# Acoustic_recorder.net
KiCad netlist of a schematic drawn in Altium Designer
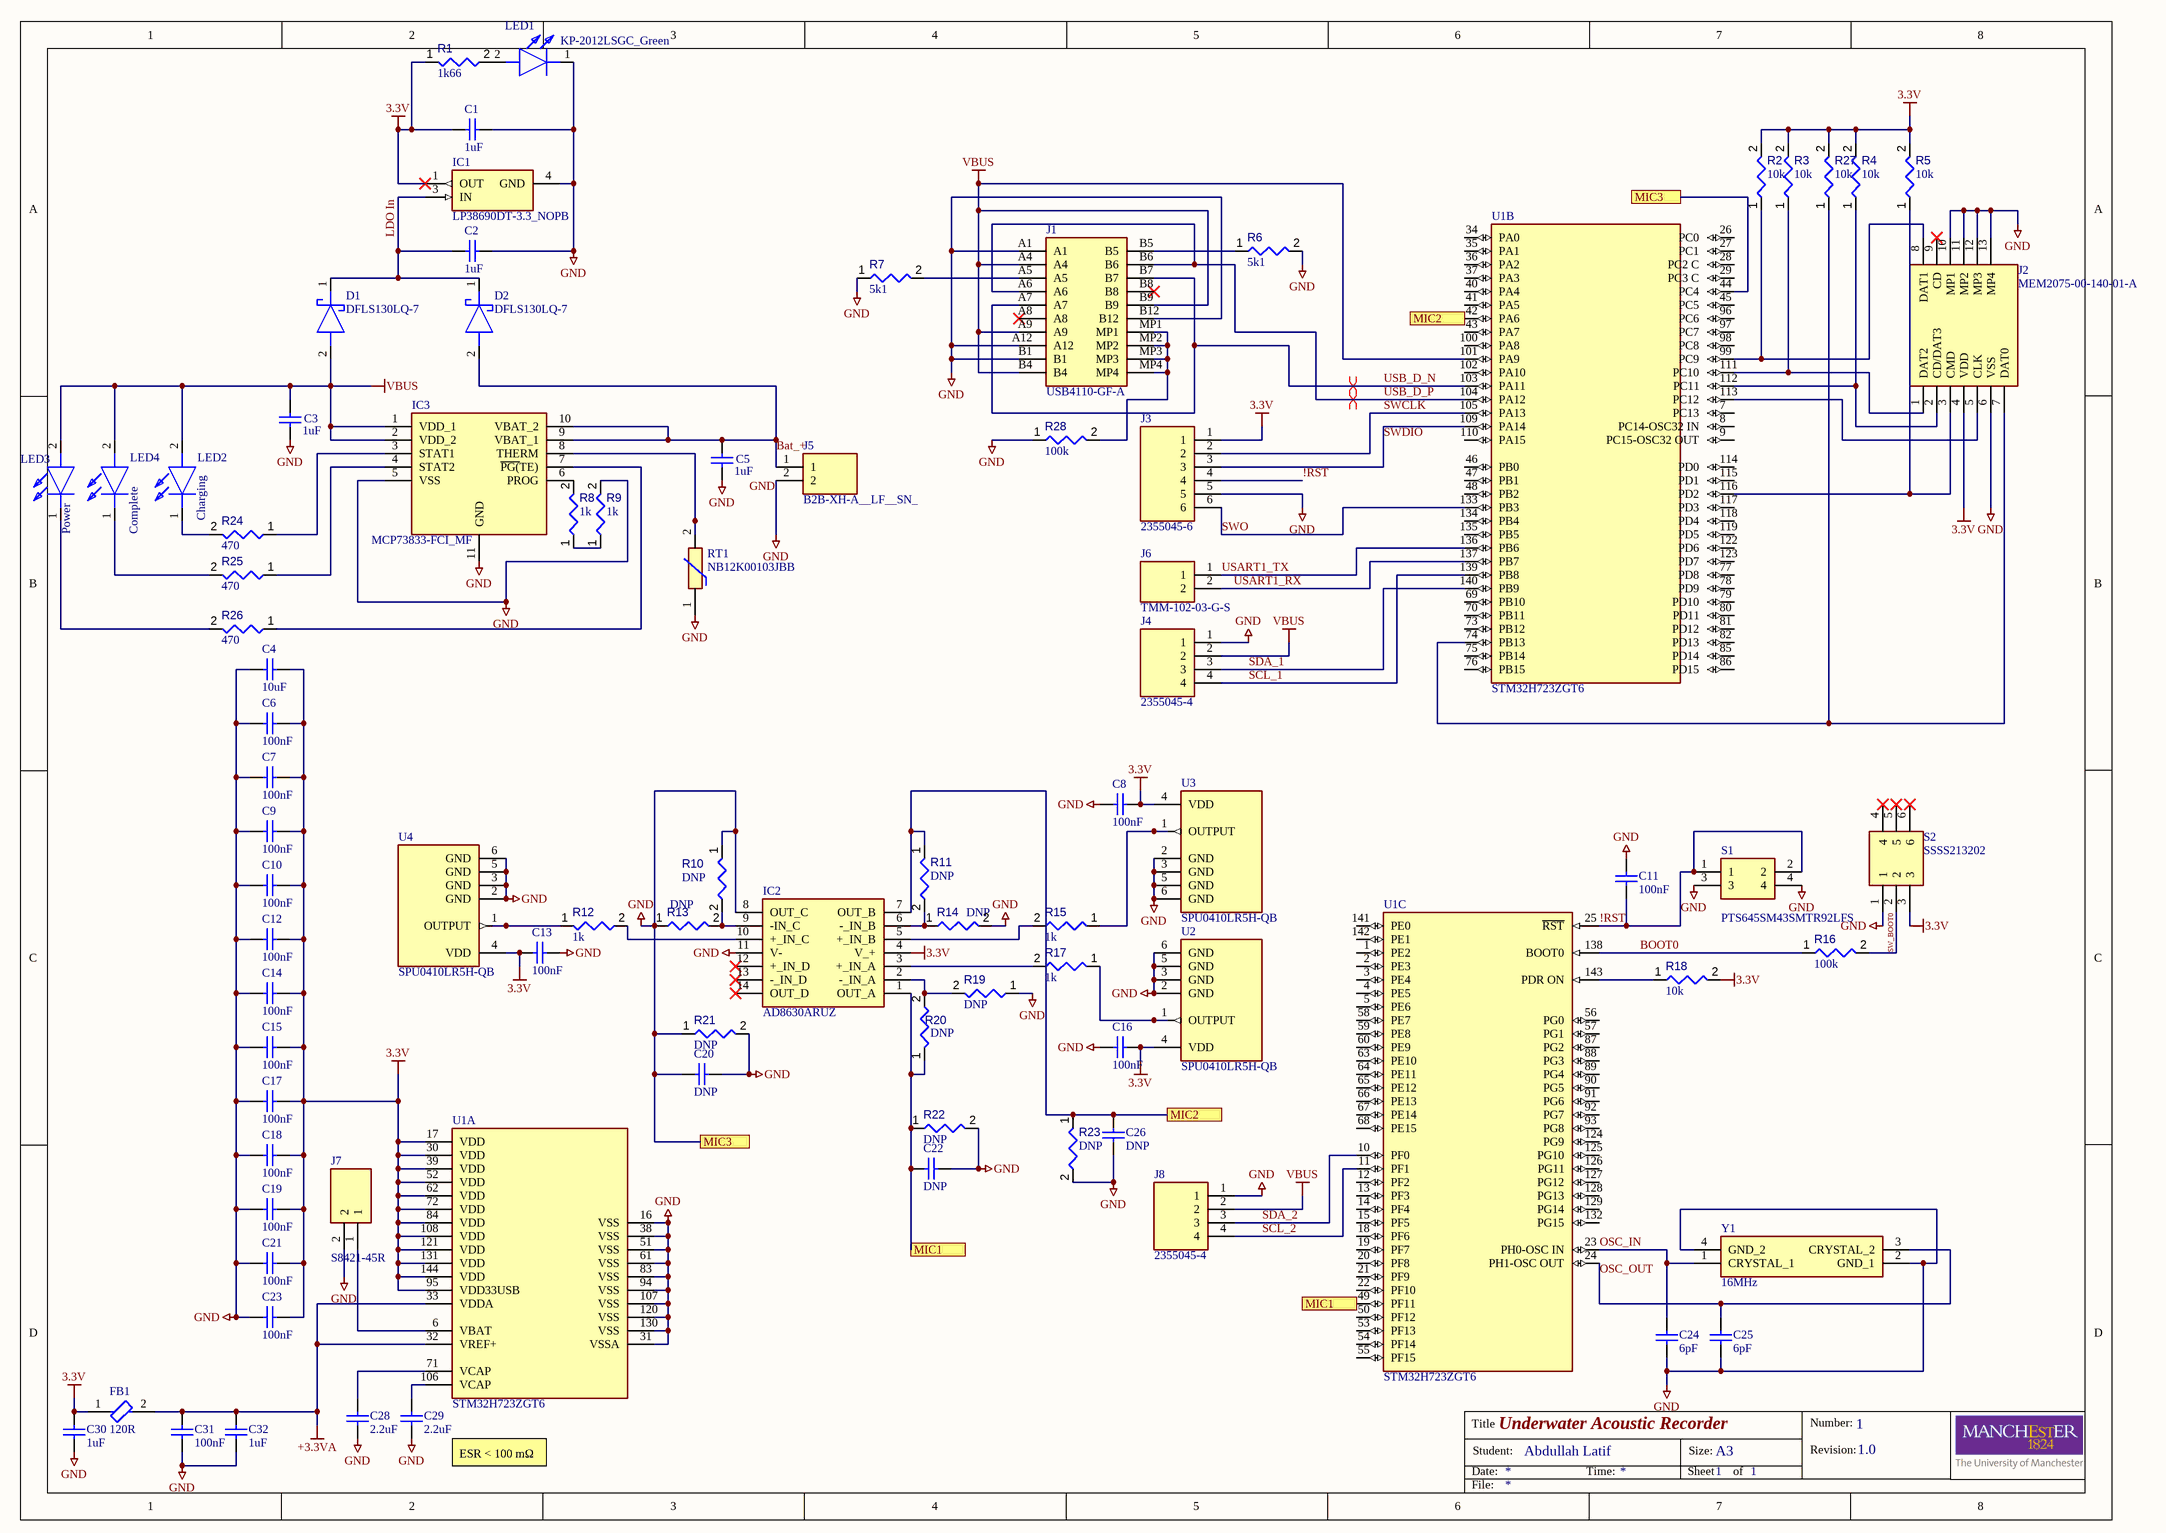
[diagram p0: Acoustic recorder.SchDoc]

(export (version "E")
  (design (tool "Eeschema 10.0.6"))
  (components
    (comp (ref "C1")
      (value "1uF")
      (footprint "CAPC2013X145X50LL20T25")
      (fields (field (name "MANUFACTURER") "Kemet") (field (name "PART NUMBER") "C0805C104K9RACTU"))
      (libsource (lib "Altium Content Vault") (part "CAP"))
    )
    (comp (ref "C2")
      (value "1uF")
      (footprint "CAPC2013X145X50LL20T25")
      (fields (field (name "MANUFACTURER") "Kemet") (field (name "PART NUMBER") "C0805C104K9RACTU"))
      (libsource (lib "Altium Content Vault") (part "CAP"))
    )
    (comp (ref "C3")
      (value "1uF")
      (footprint "CAPC2013X145X50LL20T25")
      (fields (field (name "MANUFACTURER") "Kemet") (field (name "PART NUMBER") "C0805C104K9RACTU"))
      (libsource (lib "Altium Content Vault") (part "CAP"))
    )
    (comp (ref "C4")
      (value "10uF")
      (footprint "CAPC2013X145X50LL20T25")
      (fields (field (name "MANUFACTURER") "Kemet") (field (name "PART NUMBER") "C0805C104K9RACTU"))
      (libsource (lib "Altium Content Vault") (part "CAP"))
    )
    (comp (ref "C5")
      (value "1uF")
      (footprint "CAPC2013X145X50LL20T25")
      (fields (field (name "MANUFACTURER") "Kemet") (field (name "PART NUMBER") "C0805C104K9RACTU"))
      (libsource (lib "Altium Content Vault") (part "CAP"))
    )
    (comp (ref "C6")
      (value "100nF")
      (footprint "CAPC2013X145X50LL20T25")
      (fields (field (name "MANUFACTURER") "Kemet") (field (name "PART NUMBER") "C0805C104K9RACTU"))
      (libsource (lib "Altium Content Vault") (part "CAP"))
    )
    (comp (ref "C7")
      (value "100nF")
      (footprint "CAPC2013X145X50LL20T25")
      (fields (field (name "MANUFACTURER") "Kemet") (field (name "PART NUMBER") "C0805C104K9RACTU"))
      (libsource (lib "Altium Content Vault") (part "CAP"))
    )
    (comp (ref "C8")
      (value "100nF")
      (footprint "CAPC2013X145X50LL20T25")
      (fields (field (name "MANUFACTURER") "Kemet") (field (name "PART NUMBER") "C0805C104K9RACTU"))
      (libsource (lib "Altium Content Vault") (part "CAP"))
    )
    (comp (ref "C9")
      (value "100nF")
      (footprint "CAPC2013X145X50LL20T25")
      (fields (field (name "MANUFACTURER") "Kemet") (field (name "PART NUMBER") "C0805C104K9RACTU"))
      (libsource (lib "Altium Content Vault") (part "CAP"))
    )
    (comp (ref "C10")
      (value "100nF")
      (footprint "CAPC2013X145X50LL20T25")
      (fields (field (name "MANUFACTURER") "Kemet") (field (name "PART NUMBER") "C0805C104K9RACTU"))
      (libsource (lib "Altium Content Vault") (part "CAP"))
    )
    (comp (ref "C11")
      (value "100nF")
      (footprint "CAPC2013X145X50LL20T25")
      (fields (field (name "MANUFACTURER") "Kemet") (field (name "PART NUMBER") "C0805C104K9RACTU"))
      (libsource (lib "Altium Content Vault") (part "CAP"))
    )
    (comp (ref "C12")
      (value "100nF")
      (footprint "CAPC2013X145X50LL20T25")
      (fields (field (name "MANUFACTURER") "Kemet") (field (name "PART NUMBER") "C0805C104K9RACTU"))
      (libsource (lib "Altium Content Vault") (part "CAP"))
    )
    (comp (ref "C13")
      (value "100nF")
      (footprint "CAPC2013X145X50LL20T25")
      (fields (field (name "MANUFACTURER") "Kemet") (field (name "PART NUMBER") "C0805C104K9RACTU"))
      (libsource (lib "Altium Content Vault") (part "CAP"))
    )
    (comp (ref "C14")
      (value "100nF")
      (footprint "CAPC2013X145X50LL20T25")
      (fields (field (name "MANUFACTURER") "Kemet") (field (name "PART NUMBER") "C0805C104K9RACTU"))
      (libsource (lib "Altium Content Vault") (part "CAP"))
    )
    (comp (ref "C15")
      (value "100nF")
      (footprint "CAPC2013X145X50LL20T25")
      (fields (field (name "MANUFACTURER") "Kemet") (field (name "PART NUMBER") "C0805C104K9RACTU"))
      (libsource (lib "Altium Content Vault") (part "CAP"))
    )
    (comp (ref "C16")
      (value "100nF")
      (footprint "CAPC2013X145X50LL20T25")
      (fields (field (name "MANUFACTURER") "Kemet") (field (name "PART NUMBER") "C0805C104K9RACTU"))
      (libsource (lib "Altium Content Vault") (part "CAP"))
    )
    (comp (ref "C17")
      (value "100nF")
      (footprint "CAPC2013X145X50LL20T25")
      (fields (field (name "MANUFACTURER") "Kemet") (field (name "PART NUMBER") "C0805C104K9RACTU"))
      (libsource (lib "Altium Content Vault") (part "CAP"))
    )
    (comp (ref "C18")
      (value "100nF")
      (footprint "CAPC2013X145X50LL20T25")
      (fields (field (name "MANUFACTURER") "Kemet") (field (name "PART NUMBER") "C0805C104K9RACTU"))
      (libsource (lib "Altium Content Vault") (part "CAP"))
    )
    (comp (ref "C19")
      (value "100nF")
      (footprint "CAPC2013X145X50LL20T25")
      (fields (field (name "MANUFACTURER") "Kemet") (field (name "PART NUMBER") "C0805C104K9RACTU"))
      (libsource (lib "Altium Content Vault") (part "CAP"))
    )
    (comp (ref "C20")
      (value "DNP")
      (footprint "CAPC2013X145X50LL20T25")
      (fields (field (name "MANUFACTURER") "Kemet") (field (name "PART NUMBER") "C0805C104K9RACTU"))
      (libsource (lib "Altium Content Vault") (part "CAP"))
    )
    (comp (ref "C21")
      (value "100nF")
      (footprint "CAPC2013X145X50LL20T25")
      (fields (field (name "MANUFACTURER") "Kemet") (field (name "PART NUMBER") "C0805C104K9RACTU"))
      (libsource (lib "Altium Content Vault") (part "CAP"))
    )
    (comp (ref "C22")
      (value "DNP")
      (footprint "CAPC2013X145X50LL20T25")
      (fields (field (name "MANUFACTURER") "Kemet") (field (name "PART NUMBER") "C0805C104K9RACTU"))
      (libsource (lib "Altium Content Vault") (part "CAP"))
    )
    (comp (ref "C23")
      (value "100nF")
      (footprint "CAPC2013X145X50LL20T25")
      (fields (field (name "MANUFACTURER") "Kemet") (field (name "PART NUMBER") "C0805C104K9RACTU"))
      (libsource (lib "Altium Content Vault") (part "CAP"))
    )
    (comp (ref "C24")
      (value "6pF")
      (footprint "CAPC2013X145X50LL20T25")
      (fields (field (name "MANUFACTURER") "Kemet") (field (name "PART NUMBER") "C0805C104K9RACTU"))
      (libsource (lib "Altium Content Vault") (part "CAP"))
    )
    (comp (ref "C25")
      (value "6pF")
      (footprint "CAPC2013X145X50LL20T25")
      (fields (field (name "MANUFACTURER") "Kemet") (field (name "PART NUMBER") "C0805C104K9RACTU"))
      (libsource (lib "Altium Content Vault") (part "CAP"))
    )
    (comp (ref "C26")
      (value "DNP")
      (footprint "CAPC2013X145X50LL20T25")
      (fields (field (name "MANUFACTURER") "Kemet") (field (name "PART NUMBER") "C0805C104K9RACTU"))
      (libsource (lib "Altium Content Vault") (part "CAP"))
    )
    (comp (ref "C28")
      (value "2.2uF")
      (footprint "CAPC2013X145X50LL20T25")
      (fields (field (name "MANUFACTURER") "Kemet") (field (name "PART NUMBER") "C0805C104K9RACTU"))
      (libsource (lib "Altium Content Vault") (part "CAP"))
    )
    (comp (ref "C29")
      (value "2.2uF")
      (footprint "CAPC2013X145X50LL20T25")
      (fields (field (name "MANUFACTURER") "Kemet") (field (name "PART NUMBER") "C0805C104K9RACTU"))
      (libsource (lib "Altium Content Vault") (part "CAP"))
    )
    (comp (ref "C30")
      (value "1uF")
      (footprint "CAPC2013X145X50LL20T25")
      (fields (field (name "MANUFACTURER") "Kemet") (field (name "PART NUMBER") "C0805C104K9RACTU"))
      (libsource (lib "Altium Content Vault") (part "CAP"))
    )
    (comp (ref "C31")
      (value "100nF")
      (footprint "CAPC2013X145X50LL20T25")
      (fields (field (name "MANUFACTURER") "Kemet") (field (name "PART NUMBER") "C0805C104K9RACTU"))
      (libsource (lib "Altium Content Vault") (part "CAP"))
    )
    (comp (ref "C32")
      (value "1uF")
      (footprint "CAPC2013X145X50LL20T25")
      (fields (field (name "MANUFACTURER") "Kemet") (field (name "PART NUMBER") "C0805C104K9RACTU"))
      (libsource (lib "Altium Content Vault") (part "CAP"))
    )
    (comp (ref "D1")
      (value "DFLS130LQ-7")
      (footprint "SamacSys:DFLS130LQ7")
      (description "Schottky Diode")
      (fields (field (name "MOUSER PART NUMBER") "621-DFLS130LQ7"))
      (libsource (lib "*") (part "DFLS130LQ-7"))
    )
    (comp (ref "D2")
      (value "DFLS130LQ-7")
      (footprint "SamacSys:DFLS130LQ7")
      (description "Schottky Diode")
      (fields (field (name "MOUSER PART NUMBER") "621-DFLS130LQ7"))
      (libsource (lib "*") (part "DFLS130LQ-7"))
    )
    (comp (ref "FB1")
      (value "120R")
      (footprint "FP-BLM21-0_2-t0_85-e0_5-IPC_A")
      (description "FERRITE BEAD 120 OHM 0805 1LN")
      (fields (field (name "TOLERANCE") "25%"))
      (libsource (lib "Altium Content Vault") (part "5f30dd21d616792df468990f7003faa"))
    )
    (comp (ref "IC1")
      (value "LP38690DT-3.3_NOPB")
      (footprint "SamacSys:TO228P991X238-3N")
      (description "Integrated Circuit")
      (fields
        (field (name "MANUFACTURER_PART_NUMBER") "LP38690DT-3.3/NOPB")
        (field (name "MOUSER PART NUMBER") "926-38690DT-3.3/NOPB")
      )
      (libsource (lib "*") (part "LP38690DT-3.3_NOPB"))
    )
    (comp (ref "IC2")
      (value "AD8630ARUZ")
      (footprint "SamacSys:SOP65P640X120-14N")
      (description "Integrated Circuit")
      (fields (field (name "MOUSER PART NUMBER") "584-AD8630ARUZ"))
      (libsource (lib "*") (part "AD8630ARUZ"))
    )
    (comp (ref "IC3")
      (value "MCP73833-FCI_MF")
      (footprint "SamacSys:SON50P300X300X100-11N-D")
      (description "Integrated Circuit")
      (fields
        (field (name "MANUFACTURER_PART_NUMBER") "MCP73833-FCI/MF")
        (field (name "MOUSER PART NUMBER") "579-MCP73833-FCI/MF")
      )
      (libsource (lib "*") (part "MCP73833-FCI_MF"))
    )
    (comp (ref "J1")
      (value "USB4110-GF-A")
      (footprint "SamacSys:USB4110GFA")
      (description "Connector")
      (fields (field (name "MOUSER PART NUMBER") "640-USB4110-GF-A"))
      (libsource (lib "*") (part "USB4110-GF-A"))
    )
    (comp (ref "J2")
      (value "MEM2075-00-140-01-A")
      (footprint "SamacSys:MEM20750014001A")
      (description "Connector")
      (fields (field (name "MOUSER PART NUMBER") "640-MEM20750014001A"))
      (libsource (lib "*") (part "MEM2075-00-140-01-A"))
    )
    (comp (ref "J3")
      (value "2355045-6")
      (footprint "SamacSys:HDRV6W50P0X200_1X6_1200X200X550P")
      (description "Connector")
      (fields (field (name "MOUSER PART NUMBER") "571-2355045-6"))
      (libsource (lib "*") (part "2355045-6"))
    )
    (comp (ref "J4")
      (value "2355045-4")
      (footprint "SamacSys:HDRV4W50P0X200_1X4_800X200X550P")
      (description "Connector")
      (fields (field (name "MOUSER PART NUMBER") "571-2355045-4"))
      (libsource (lib "*") (part "2355045-4"))
    )
    (comp (ref "J5")
      (value "B2B-XH-A__LF__SN_")
      (footprint "SamacSys:SHDR2W64P0X250_1X2_740X575X700P")
      (description "Connector")
      (fields (field (name "MANUFACTURER_PART_NUMBER") "B2B-XH-A (LF)(SN)"))
      (libsource (lib "*") (part "B2B-XH-A__LF__SN_"))
    )
    (comp (ref "J6")
      (value "TMM-102-03-G-S")
      (footprint "SamacSys:HDRV2W50P0X200_1X2_400X197X550P")
      (description "Connector")
      (fields (field (name "MOUSER PART NUMBER") "200-TMM10203GS"))
      (libsource (lib "*") (part "TMM-102-03-G-S"))
    )
    (comp (ref "J7")
      (value "S8421-45R")
      (footprint "SamacSys:S8421-45R_1")
      (description "Connector")
      (fields (field (name "MOUSER PART NUMBER") "855-S8421-45R"))
      (libsource (lib "*") (part "S8421-45R"))
    )
    (comp (ref "J8")
      (value "2355045-4")
      (footprint "SamacSys:HDRV4W50P0X200_1X4_800X200X550P")
      (description "Connector")
      (fields (field (name "MOUSER PART NUMBER") "571-2355045-4"))
      (libsource (lib "*") (part "2355045-4"))
    )
    (comp (ref "LED1")
      (value "KP-2012LSGC_Green")
      (footprint "SamacSys:LEDC2012X110N")
      (description "LED")
      (fields (field (name "MANUFACTURER_PART_NUMBER") "KP-2012LSGC"))
      (libsource (lib "*") (part "KP-2012LSGC"))
    )
    (comp (ref "LED2")
      (value "Charging")
      (footprint "SamacSys:LEDC2012X110N")
      (description "LED")
      (fields (field (name "MANUFACTURER_PART_NUMBER") "KP-2012LSGC"))
      (libsource (lib "*") (part "KP-2012LSGC"))
    )
    (comp (ref "LED3")
      (value "Power")
      (footprint "SamacSys:LEDC2012X110N")
      (description "LED")
      (fields (field (name "MANUFACTURER_PART_NUMBER") "KP-2012LSGC"))
      (libsource (lib "*") (part "KP-2012LSGC"))
    )
    (comp (ref "LED4")
      (value "Complete")
      (footprint "SamacSys:LEDC2012X110N")
      (description "LED")
      (fields (field (name "MANUFACTURER_PART_NUMBER") "KP-2012LSGC"))
      (libsource (lib "*") (part "KP-2012LSGC"))
    )
    (comp (ref "R1")
      (value "1k66")
      (footprint "RESC2013X50X35ML15T15")
      (fields (field (name "TOLERANCE") "1%") (field (name "POWER") "125mW"))
      (libsource (lib "The University of Manchester") (part "RES-2"))
    )
    (comp (ref "R2")
      (value "10k")
      (footprint "RESC2013X50X35ML15T15")
      (description "Chip Resistor, 10 KOhm, +/- 1%, 125 mW, -55 to 155 degC, 0805 (2012 Metric)")
      (fields (field (name "TOLERANCE") "1%") (field (name "POWER") "125mW"))
      (libsource (lib "The University of Manchester") (part "RES-2"))
    )
    (comp (ref "R3")
      (value "10k")
      (footprint "RESC2013X50X35ML15T15")
      (description "Chip Resistor, 10 KOhm, +/- 1%, 125 mW, -55 to 155 degC, 0805 (2012 Metric)")
      (fields (field (name "TOLERANCE") "1%") (field (name "POWER") "125mW"))
      (libsource (lib "The University of Manchester") (part "RES-2"))
    )
    (comp (ref "R4")
      (value "10k")
      (footprint "RESC2013X50X35ML15T15")
      (description "Chip Resistor, 10 KOhm, +/- 1%, 125 mW, -55 to 155 degC, 0805 (2012 Metric)")
      (fields (field (name "TOLERANCE") "1%") (field (name "POWER") "125mW"))
      (libsource (lib "The University of Manchester") (part "RES-2"))
    )
    (comp (ref "R5")
      (value "10k")
      (footprint "RESC2013X50X35ML15T15")
      (description "Chip Resistor, 10 KOhm, +/- 1%, 125 mW, -55 to 155 degC, 0805 (2012 Metric)")
      (fields (field (name "TOLERANCE") "1%") (field (name "POWER") "125mW"))
      (libsource (lib "The University of Manchester") (part "RES-2"))
    )
    (comp (ref "R6")
      (value "5k1")
      (footprint "RESC2013X50X35ML15T15")
      (fields (field (name "TOLERANCE") "1%") (field (name "POWER") "125mW"))
      (libsource (lib "The University of Manchester") (part "RES-2"))
    )
    (comp (ref "R7")
      (value "5k1")
      (footprint "RESC2013X50X35ML15T15")
      (fields (field (name "TOLERANCE") "1%") (field (name "POWER") "125mW"))
      (libsource (lib "The University of Manchester") (part "RES-2"))
    )
    (comp (ref "R8")
      (value "1k")
      (footprint "RESC2013X50X35ML15T15")
      (fields (field (name "TOLERANCE") "1%") (field (name "POWER") "125mW"))
      (libsource (lib "The University of Manchester") (part "RES-2"))
    )
    (comp (ref "R9")
      (value "1k")
      (footprint "RESC2013X50X35ML15T15")
      (fields (field (name "TOLERANCE") "1%") (field (name "POWER") "125mW"))
      (libsource (lib "The University of Manchester") (part "RES-2"))
    )
    (comp (ref "R10")
      (value "DNP")
      (footprint "RESC2013X50X35ML15T15")
      (description "2k1")
      (fields (field (name "TOLERANCE") "1%") (field (name "POWER") "125mW"))
      (libsource (lib "The University of Manchester") (part "RES-2"))
    )
    (comp (ref "R11")
      (value "DNP")
      (footprint "RESC2013X50X35ML15T15")
      (description "2k1")
      (fields (field (name "TOLERANCE") "1%") (field (name "POWER") "125mW"))
      (libsource (lib "The University of Manchester") (part "RES-2"))
    )
    (comp (ref "R12")
      (value "1k")
      (footprint "RESC2013X50X35ML15T15")
      (fields (field (name "TOLERANCE") "1%") (field (name "POWER") "125mW"))
      (libsource (lib "The University of Manchester") (part "RES-2"))
    )
    (comp (ref "R13")
      (value "DNP")
      (footprint "RESC2013X50X35ML15T15")
      (description "1k2")
      (fields (field (name "TOLERANCE") "1%") (field (name "POWER") "125mW"))
      (libsource (lib "The University of Manchester") (part "RES-2"))
    )
    (comp (ref "R14")
      (value "DNP")
      (footprint "RESC2013X50X35ML15T15")
      (description "1k2")
      (fields (field (name "TOLERANCE") "1%") (field (name "POWER") "125mW"))
      (libsource (lib "The University of Manchester") (part "RES-2"))
    )
    (comp (ref "R15")
      (value "1k")
      (footprint "RESC2013X50X35ML15T15")
      (fields (field (name "TOLERANCE") "1%") (field (name "POWER") "125mW"))
      (libsource (lib "The University of Manchester") (part "RES-2"))
    )
    (comp (ref "R16")
      (value "100k")
      (footprint "RESC2013X50X35ML15T15")
      (fields (field (name "TOLERANCE") "1%") (field (name "POWER") "125mW"))
      (libsource (lib "The University of Manchester") (part "RES-2"))
    )
    (comp (ref "R17")
      (value "1k")
      (footprint "RESC2013X50X35ML15T15")
      (fields (field (name "TOLERANCE") "1%") (field (name "POWER") "125mW"))
      (libsource (lib "The University of Manchester") (part "RES-2"))
    )
    (comp (ref "R18")
      (value "10k")
      (footprint "RESC2013X50X35ML15T15")
      (fields (field (name "TOLERANCE") "1%") (field (name "POWER") "125mW"))
      (libsource (lib "The University of Manchester") (part "RES-2"))
    )
    (comp (ref "R19")
      (value "DNP")
      (footprint "RESC2013X50X35ML15T15")
      (description "1k2")
      (fields (field (name "TOLERANCE") "1%") (field (name "POWER") "125mW"))
      (libsource (lib "The University of Manchester") (part "RES-2"))
    )
    (comp (ref "R20")
      (value "DNP")
      (footprint "RESC2013X50X35ML15T15")
      (description "2k1")
      (fields (field (name "TOLERANCE") "1%") (field (name "POWER") "125mW"))
      (libsource (lib "The University of Manchester") (part "RES-2"))
    )
    (comp (ref "R21")
      (value "DNP")
      (footprint "RESC2013X50X35ML15T15")
      (description "100k")
      (fields (field (name "TOLERANCE") "1%") (field (name "POWER") "125mW"))
      (libsource (lib "The University of Manchester") (part "RES-2"))
    )
    (comp (ref "R22")
      (value "DNP")
      (footprint "RESC2013X50X35ML15T15")
      (description "100k")
      (fields (field (name "TOLERANCE") "1%") (field (name "POWER") "125mW"))
      (libsource (lib "The University of Manchester") (part "RES-2"))
    )
    (comp (ref "R23")
      (value "DNP")
      (footprint "RESC2013X50X35ML15T15")
      (description "100k")
      (fields (field (name "TOLERANCE") "1%") (field (name "POWER") "125mW"))
      (libsource (lib "The University of Manchester") (part "RES-2"))
    )
    (comp (ref "R24")
      (value "470")
      (footprint "RESC2013X50X35ML15T15")
      (description "1k")
      (fields (field (name "TOLERANCE") "1%") (field (name "POWER") "125mW"))
      (libsource (lib "The University of Manchester") (part "RES-2"))
    )
    (comp (ref "R25")
      (value "470")
      (footprint "RESC2013X50X35ML15T15")
      (description "1k")
      (fields (field (name "TOLERANCE") "1%") (field (name "POWER") "125mW"))
      (libsource (lib "The University of Manchester") (part "RES-2"))
    )
    (comp (ref "R26")
      (value "470")
      (footprint "RESC2013X50X35ML15T15")
      (description "1k")
      (fields (field (name "TOLERANCE") "1%") (field (name "POWER") "125mW"))
      (libsource (lib "The University of Manchester") (part "RES-2"))
    )
    (comp (ref "R27")
      (value "10k")
      (footprint "RESC2013X50X35ML15T15")
      (description "Chip Resistor, 10 KOhm, +/- 1%, 125 mW, -55 to 155 degC, 0805 (2012 Metric)")
      (fields (field (name "TOLERANCE") "1%") (field (name "POWER") "125mW"))
      (libsource (lib "The University of Manchester") (part "RES-2"))
    )
    (comp (ref "R28")
      (value "100k")
      (footprint "RESC2013X50X35ML15T15")
      (fields (field (name "TOLERANCE") "1%") (field (name "POWER") "125mW"))
      (libsource (lib "The University of Manchester") (part "RES-2"))
    )
    (comp (ref "RT1")
      (value "NB12K00103JBB")
      (footprint "SamacSys:RESC2212X50N")
      (description "Thermistor")
      (fields (field (name "MOUSER PART NUMBER") "581-NB12K00103JBB"))
      (libsource (lib "SamacSys") (part "NB12K00103JBB"))
    )
    (comp (ref "S1")
      (value "PTS645SM43SMTR92LFS")
      (footprint "SamacSys:PTS645(SMT)")
      (description "Switch")
      (fields (field (name "MOUSER PART NUMBER") "611-PTS645SM43SMTR92"))
      (libsource (lib "*") (part "PTS645SM43SMTR92LFS"))
    )
    (comp (ref "S2")
      (value "SSSS213202")
      (footprint "SamacSys:SSSS213202")
      (description "Switch")
      (fields (field (name "MOUSER PART NUMBER") "688-SSSS213202"))
      (libsource (lib "*") (part "SSSS213202"))
    )
    (comp (ref "U1")
      (value "STM32H723ZGT6")
      (footprint "FP-LQFP144-1A-IPC_A")
      (description "IC MCU 32BIT 1MB FLASH 144LQFP")
      (libsource (lib "Altium Content Vault") (part "099c9e622ff36f7eb897f9cba6d1f51"))
    )
    (comp (ref "U2")
      (value "SPU0410LR5H-QB")
      (footprint "XDCR_SPU0410LR5H-QB")
      (fields (field (name "MF") "Knowles"))
      (libsource (lib "") (part "SPU0410LR5H-QB_1"))
    )
    (comp (ref "U3")
      (value "SPU0410LR5H-QB")
      (footprint "XDCR_SPU0410LR5H-QB")
      (fields (field (name "MF") "Knowles"))
      (libsource (lib "SPU0410LR5H-QB") (part "SPU0410LR5H-QB"))
    )
    (comp (ref "U4")
      (value "SPU0410LR5H-QB")
      (footprint "XDCR_SPU0410LR5H-QB")
      (fields (field (name "MF") "Knowles"))
      (libsource (lib "") (part "SPU0410LR5H-QB_2"))
    )
    (comp (ref "Y1")
      (value "16MHz")
      (footprint "SamacSys:CX3225SA16000D0PSTZ1")
      (description "Crystal or Oscillator")
      (fields
        (field (name "MANUFACTURER_PART_NUMBER") "CX3225SA16000D0PSTZ1")
        (field (name "MOUSER PART NUMBER") "581-CX3225SA16D0PST")
      )
      (libsource (lib "*") (part "CX3225SA16000D0PSTZ1"))
    )
  )
  (nets
    (net (code "1") (name "+3.3VA") (class "Default")
      (node (ref "C31") (pin "2") (pinfunction "2_2") (pintype "passive"))
      (node (ref "C32") (pin "2") (pinfunction "2_2") (pintype "passive"))
      (node (ref "FB1") (pin "2") (pinfunction "2_2") (pintype "passive"))
      (node (ref "U1") (pin "32") (pinfunction "VREF+_32") (pintype "power_in"))
      (node (ref "U1") (pin "33") (pinfunction "VDDA_33") (pintype "power_in"))
    )
    (net (code "2") (name "/!RST") (class "Default")
      (node (ref "C11") (pin "1") (pinfunction "1_1") (pintype "passive"))
      (node (ref "J3") (pin "4") (pinfunction "4_4") (pintype "passive"))
      (node (ref "S1") (pin "1") (pinfunction "1_1") (pintype "passive"))
      (node (ref "S1") (pin "2") (pinfunction "2_2") (pintype "passive"))
      (node (ref "U1") (pin "25") (pinfunction "~{RST}_25") (pintype "input"))
    )
    (net (code "3") (name "/BOOT0") (class "Default")
      (node (ref "R16") (pin "1") (pinfunction "1_1") (pintype "passive"))
      (node (ref "U1") (pin "138") (pinfunction "BOOT0_138") (pintype "input"))
    )
    (net (code "4") (name "/Bat_+") (class "Default")
      (node (ref "C5") (pin "2") (pinfunction "2_2") (pintype "passive"))
      (node (ref "D2") (pin "2") (pinfunction "A_2") (pintype "passive"))
      (node (ref "IC3") (pin "10") (pinfunction "VBAT_2_10") (pintype "passive"))
      (node (ref "IC3") (pin "9") (pinfunction "VBAT_1_9") (pintype "passive"))
      (node (ref "J5") (pin "1") (pinfunction "1_1") (pintype "passive"))
    )
    (net (code "5") (name "/LDO In") (class "Default")
      (node (ref "C2") (pin "1") (pinfunction "1_1") (pintype "passive"))
      (node (ref "D1") (pin "1") (pinfunction "K_1") (pintype "passive"))
      (node (ref "D2") (pin "1") (pinfunction "K_1") (pintype "passive"))
      (node (ref "IC1") (pin "3") (pinfunction "IN_3") (pintype "input"))
    )
    (net (code "6") (name "/MIC1") (class "Default")
      (node (ref "C22") (pin "1") (pinfunction "1_1") (pintype "passive"))
      (node (ref "IC2") (pin "1") (pinfunction "OUT_A_1") (pintype "passive"))
      (node (ref "R20") (pin "1") (pinfunction "1_1") (pintype "passive"))
      (node (ref "R22") (pin "1") (pinfunction "1_1") (pintype "passive"))
      (node (ref "U1") (pin "49") (pinfunction "PF11_49") (pintype "bidirectional"))
    )
    (net (code "7") (name "/MIC2") (class "Default")
      (node (ref "C26") (pin "1") (pinfunction "1_1") (pintype "passive"))
      (node (ref "IC2") (pin "7") (pinfunction "OUT_B_7") (pintype "passive"))
      (node (ref "R11") (pin "1") (pinfunction "1_1") (pintype "passive"))
      (node (ref "R23") (pin "1") (pinfunction "1_1") (pintype "passive"))
      (node (ref "U1") (pin "42") (pinfunction "PA6_42") (pintype "bidirectional"))
    )
    (net (code "8") (name "/OSC_IN") (class "Default")
      (node (ref "C24") (pin "1") (pinfunction "1_1") (pintype "passive"))
      (node (ref "U1") (pin "23") (pinfunction "PH0-OSC_IN_23") (pintype "bidirectional"))
      (node (ref "Y1") (pin "1") (pinfunction "CRYSTAL_1_1") (pintype "passive"))
    )
    (net (code "9") (name "/OSC_OUT") (class "Default")
      (node (ref "C25") (pin "2") (pinfunction "2_2") (pintype "passive"))
      (node (ref "U1") (pin "24") (pinfunction "PH1-OSC_OUT_24") (pintype "bidirectional"))
      (node (ref "Y1") (pin "3") (pinfunction "CRYSTAL_2_3") (pintype "passive"))
    )
    (net (code "10") (name "/SCL_1") (class "Default")
      (node (ref "J4") (pin "4") (pinfunction "4_4") (pintype "passive"))
      (node (ref "U1") (pin "139") (pinfunction "PB8_139") (pintype "bidirectional"))
    )
    (net (code "11") (name "/SCL_2") (class "Default")
      (node (ref "J8") (pin "4") (pinfunction "4_4") (pintype "passive"))
      (node (ref "U1") (pin "11") (pinfunction "PF1_11") (pintype "bidirectional"))
    )
    (net (code "12") (name "/SDA_1") (class "Default")
      (node (ref "J4") (pin "3") (pinfunction "3_3") (pintype "passive"))
      (node (ref "U1") (pin "140") (pinfunction "PB9_140") (pintype "bidirectional"))
    )
    (net (code "13") (name "/SDA_2") (class "Default")
      (node (ref "J8") (pin "3") (pinfunction "3_3") (pintype "passive"))
      (node (ref "U1") (pin "10") (pinfunction "PF0_10") (pintype "bidirectional"))
    )
    (net (code "14") (name "/SWCLK") (class "Default")
      (node (ref "J3") (pin "2") (pinfunction "2_2") (pintype "passive"))
      (node (ref "U1") (pin "105") (pinfunction "PA13_105") (pintype "bidirectional"))
    )
    (net (code "15") (name "/SWDIO") (class "Default")
      (node (ref "J3") (pin "3") (pinfunction "3_3") (pintype "passive"))
      (node (ref "U1") (pin "109") (pinfunction "PA14_109") (pintype "bidirectional"))
    )
    (net (code "16") (name "/SWO") (class "Default")
      (node (ref "J3") (pin "6") (pinfunction "6_6") (pintype "passive"))
      (node (ref "U1") (pin "133") (pinfunction "PB3_133") (pintype "bidirectional"))
    )
    (net (code "17") (name "/SW_BOOT0") (class "Default")
      (node (ref "R16") (pin "2") (pinfunction "2_2") (pintype "passive"))
      (node (ref "S2") (pin "2") (pinfunction "2_2") (pintype "passive"))
    )
    (net (code "18") (name "/USART1_RX") (class "Default")
      (node (ref "J6") (pin "2") (pinfunction "2_2") (pintype "passive"))
      (node (ref "U1") (pin "137") (pinfunction "PB7_137") (pintype "bidirectional"))
    )
    (net (code "19") (name "/USART1_TX") (class "Default")
      (node (ref "J6") (pin "1") (pinfunction "1_1") (pintype "passive"))
      (node (ref "U1") (pin "136") (pinfunction "PB6_136") (pintype "bidirectional"))
    )
    (net (code "20") (name "/USB_D_N") (class "Default")
      (node (ref "J1") (pin "A7") (pinfunction "A7_A7") (pintype "passive"))
      (node (ref "J1") (pin "B7") (pinfunction "B7_B7") (pintype "passive"))
      (node (ref "U1") (pin "103") (pinfunction "PA11_103") (pintype "bidirectional"))
    )
    (net (code "21") (name "/USB_D_P") (class "Default")
      (node (ref "J1") (pin "A6") (pinfunction "A6_A6") (pintype "passive"))
      (node (ref "J1") (pin "B6") (pinfunction "B6_B6") (pintype "passive"))
      (node (ref "U1") (pin "104") (pinfunction "PA12_104") (pintype "bidirectional"))
    )
    (net (code "22") (name "3.3V") (class "Default")
      (node (ref "C1") (pin "1") (pinfunction "1_1") (pintype "passive"))
      (node (ref "C10") (pin "1") (pinfunction "1_1") (pintype "passive"))
      (node (ref "C12") (pin "1") (pinfunction "1_1") (pintype "passive"))
      (node (ref "C13") (pin "1") (pinfunction "1_1") (pintype "passive"))
      (node (ref "C14") (pin "1") (pinfunction "1_1") (pintype "passive"))
      (node (ref "C15") (pin "2") (pinfunction "2_2") (pintype "passive"))
      (node (ref "C16") (pin "1") (pinfunction "1_1") (pintype "passive"))
      (node (ref "C17") (pin "2") (pinfunction "2_2") (pintype "passive"))
      (node (ref "C18") (pin "2") (pinfunction "2_2") (pintype "passive"))
      (node (ref "C19") (pin "2") (pinfunction "2_2") (pintype "passive"))
      (node (ref "C21") (pin "2") (pinfunction "2_2") (pintype "passive"))
      (node (ref "C23") (pin "2") (pinfunction "2_2") (pintype "passive"))
      (node (ref "C30") (pin "2") (pinfunction "2_2") (pintype "passive"))
      (node (ref "C4") (pin "1") (pinfunction "1_1") (pintype "passive"))
      (node (ref "C6") (pin "1") (pinfunction "1_1") (pintype "passive"))
      (node (ref "C7") (pin "1") (pinfunction "1_1") (pintype "passive"))
      (node (ref "C8") (pin "1") (pinfunction "1_1") (pintype "passive"))
      (node (ref "C9") (pin "1") (pinfunction "1_1") (pintype "passive"))
      (node (ref "FB1") (pin "1") (pinfunction "1_1") (pintype "passive"))
      (node (ref "IC1") (pin "1") (pinfunction "OUT_1") (pintype "output"))
      (node (ref "IC2") (pin "4") (pinfunction "V_+_4") (pintype "passive"))
      (node (ref "J2") (pin "4") (pinfunction "VDD_4") (pintype "passive"))
      (node (ref "J3") (pin "1") (pinfunction "1_1") (pintype "passive"))
      (node (ref "R1") (pin "1") (pinfunction "1_1") (pintype "passive"))
      (node (ref "R18") (pin "2") (pinfunction "2_2") (pintype "passive"))
      (node (ref "R2") (pin "2") (pinfunction "2_2") (pintype "passive"))
      (node (ref "R27") (pin "2") (pinfunction "2_2") (pintype "passive"))
      (node (ref "R3") (pin "2") (pinfunction "2_2") (pintype "passive"))
      (node (ref "R4") (pin "2") (pinfunction "2_2") (pintype "passive"))
      (node (ref "R5") (pin "2") (pinfunction "2_2") (pintype "passive"))
      (node (ref "S2") (pin "3") (pinfunction "3_3") (pintype "passive"))
      (node (ref "U1") (pin "108") (pinfunction "VDD_108") (pintype "power_in"))
      (node (ref "U1") (pin "121") (pinfunction "VDD_121") (pintype "power_in"))
      (node (ref "U1") (pin "131") (pinfunction "VDD_131") (pintype "power_in"))
      (node (ref "U1") (pin "144") (pinfunction "VDD_144") (pintype "power_in"))
      (node (ref "U1") (pin "17") (pinfunction "VDD_17") (pintype "power_in"))
      (node (ref "U1") (pin "30") (pinfunction "VDD_30") (pintype "power_in"))
      (node (ref "U1") (pin "39") (pinfunction "VDD_39") (pintype "power_in"))
      (node (ref "U1") (pin "52") (pinfunction "VDD_52") (pintype "power_in"))
      (node (ref "U1") (pin "62") (pinfunction "VDD_62") (pintype "power_in"))
      (node (ref "U1") (pin "72") (pinfunction "VDD_72") (pintype "power_in"))
      (node (ref "U1") (pin "84") (pinfunction "VDD_84") (pintype "power_in"))
      (node (ref "U1") (pin "95") (pinfunction "VDD33USB_95") (pintype "power_in"))
      (node (ref "U2") (pin "4") (pinfunction "VDD_4") (pintype "power_in"))
      (node (ref "U3") (pin "4") (pinfunction "VDD_4") (pintype "power_in"))
      (node (ref "U4") (pin "4") (pinfunction "VDD_4") (pintype "power_in"))
    )
    (net (code "23") (name "GND") (class "Default")
      (node (ref "C1") (pin "2") (pinfunction "2_2") (pintype "passive"))
      (node (ref "C10") (pin "2") (pinfunction "2_2") (pintype "passive"))
      (node (ref "C11") (pin "2") (pinfunction "2_2") (pintype "passive"))
      (node (ref "C12") (pin "2") (pinfunction "2_2") (pintype "passive"))
      (node (ref "C13") (pin "2") (pinfunction "2_2") (pintype "passive"))
      (node (ref "C14") (pin "2") (pinfunction "2_2") (pintype "passive"))
      (node (ref "C15") (pin "1") (pinfunction "1_1") (pintype "passive"))
      (node (ref "C16") (pin "2") (pinfunction "2_2") (pintype "passive"))
      (node (ref "C17") (pin "1") (pinfunction "1_1") (pintype "passive"))
      (node (ref "C18") (pin "1") (pinfunction "1_1") (pintype "passive"))
      (node (ref "C19") (pin "1") (pinfunction "1_1") (pintype "passive"))
      (node (ref "C2") (pin "2") (pinfunction "2_2") (pintype "passive"))
      (node (ref "C20") (pin "1") (pinfunction "1_1") (pintype "passive"))
      (node (ref "C20") (pin "2") (pinfunction "2_2") (pintype "passive"))
      (node (ref "C21") (pin "1") (pinfunction "1_1") (pintype "passive"))
      (node (ref "C22") (pin "2") (pinfunction "2_2") (pintype "passive"))
      (node (ref "C23") (pin "1") (pinfunction "1_1") (pintype "passive"))
      (node (ref "C24") (pin "2") (pinfunction "2_2") (pintype "passive"))
      (node (ref "C25") (pin "1") (pinfunction "1_1") (pintype "passive"))
      (node (ref "C26") (pin "2") (pinfunction "2_2") (pintype "passive"))
      (node (ref "C28") (pin "1") (pinfunction "1_1") (pintype "passive"))
      (node (ref "C29") (pin "1") (pinfunction "1_1") (pintype "passive"))
      (node (ref "C3") (pin "1") (pinfunction "1_1") (pintype "passive"))
      (node (ref "C30") (pin "1") (pinfunction "1_1") (pintype "passive"))
      (node (ref "C31") (pin "1") (pinfunction "1_1") (pintype "passive"))
      (node (ref "C32") (pin "1") (pinfunction "1_1") (pintype "passive"))
      (node (ref "C4") (pin "2") (pinfunction "2_2") (pintype "passive"))
      (node (ref "C5") (pin "1") (pinfunction "1_1") (pintype "passive"))
      (node (ref "C6") (pin "2") (pinfunction "2_2") (pintype "passive"))
      (node (ref "C7") (pin "2") (pinfunction "2_2") (pintype "passive"))
      (node (ref "C8") (pin "2") (pinfunction "2_2") (pintype "passive"))
      (node (ref "C9") (pin "2") (pinfunction "2_2") (pintype "passive"))
      (node (ref "IC1") (pin "4") (pinfunction "GND_4") (pintype "power_in"))
      (node (ref "IC2") (pin "11") (pinfunction "V-_11") (pintype "passive"))
      (node (ref "IC2") (pin "8") (pinfunction "OUT_C_8") (pintype "passive"))
      (node (ref "IC3") (pin "11") (pinfunction "GND_11") (pintype "passive"))
      (node (ref "IC3") (pin "5") (pinfunction "VSS_5") (pintype "passive"))
      (node (ref "J1") (pin "A1") (pinfunction "A1_A1") (pintype "passive"))
      (node (ref "J1") (pin "A12") (pinfunction "A12_A12") (pintype "passive"))
      (node (ref "J1") (pin "B1") (pinfunction "B1_B1") (pintype "passive"))
      (node (ref "J1") (pin "B12") (pinfunction "B12_B12") (pintype "passive"))
      (node (ref "J2") (pin "10") (pinfunction "MP1_10") (pintype "passive"))
      (node (ref "J2") (pin "11") (pinfunction "MP2_11") (pintype "passive"))
      (node (ref "J2") (pin "12") (pinfunction "MP3_12") (pintype "passive"))
      (node (ref "J2") (pin "13") (pinfunction "MP4_13") (pintype "passive"))
      (node (ref "J2") (pin "6") (pinfunction "VSS_6") (pintype "passive"))
      (node (ref "J3") (pin "5") (pinfunction "5_5") (pintype "passive"))
      (node (ref "J4") (pin "1") (pinfunction "1_1") (pintype "passive"))
      (node (ref "J5") (pin "2") (pinfunction "2_2") (pintype "passive"))
      (node (ref "J7") (pin "2") (pinfunction "2_2") (pintype "passive"))
      (node (ref "J8") (pin "1") (pinfunction "1_1") (pintype "passive"))
      (node (ref "LED1") (pin "1") (pinfunction "K_1") (pintype "passive"))
      (node (ref "R10") (pin "1") (pinfunction "1_1") (pintype "passive"))
      (node (ref "R13") (pin "1") (pinfunction "1_1") (pintype "passive"))
      (node (ref "R14") (pin "2") (pinfunction "2_2") (pintype "passive"))
      (node (ref "R19") (pin "1") (pinfunction "1_1") (pintype "passive"))
      (node (ref "R21") (pin "1") (pinfunction "1_1") (pintype "passive"))
      (node (ref "R21") (pin "2") (pinfunction "2_2") (pintype "passive"))
      (node (ref "R22") (pin "2") (pinfunction "2_2") (pintype "passive"))
      (node (ref "R23") (pin "2") (pinfunction "2_2") (pintype "passive"))
      (node (ref "R28") (pin "1") (pinfunction "1_1") (pintype "passive"))
      (node (ref "R6") (pin "2") (pinfunction "2_2") (pintype "passive"))
      (node (ref "R7") (pin "1") (pinfunction "1_1") (pintype "passive"))
      (node (ref "R9") (pin "2") (pinfunction "2_2") (pintype "passive"))
      (node (ref "RT1") (pin "1") (pinfunction "1_1") (pintype "passive"))
      (node (ref "S1") (pin "3") (pinfunction "3_3") (pintype "passive"))
      (node (ref "S1") (pin "4") (pinfunction "4_4") (pintype "passive"))
      (node (ref "S2") (pin "1") (pinfunction "1_1") (pintype "passive"))
      (node (ref "U1") (pin "107") (pinfunction "VSS_107") (pintype "power_in"))
      (node (ref "U1") (pin "120") (pinfunction "VSS_120") (pintype "power_in"))
      (node (ref "U1") (pin "130") (pinfunction "VSS_130") (pintype "power_in"))
      (node (ref "U1") (pin "16") (pinfunction "VSS_16") (pintype "power_in"))
      (node (ref "U1") (pin "31") (pinfunction "VSSA_31") (pintype "power_in"))
      (node (ref "U1") (pin "38") (pinfunction "VSS_38") (pintype "power_in"))
      (node (ref "U1") (pin "44") (pinfunction "PC4_44") (pintype "bidirectional"))
      (node (ref "U1") (pin "51") (pinfunction "VSS_51") (pintype "power_in"))
      (node (ref "U1") (pin "61") (pinfunction "VSS_61") (pintype "power_in"))
      (node (ref "U1") (pin "83") (pinfunction "VSS_83") (pintype "power_in"))
      (node (ref "U1") (pin "94") (pinfunction "VSS_94") (pintype "power_in"))
      (node (ref "U2") (pin "2") (pinfunction "GND_2") (pintype "power_in"))
      (node (ref "U2") (pin "3") (pinfunction "GND_3") (pintype "power_in"))
      (node (ref "U2") (pin "5") (pinfunction "GND_5") (pintype "power_in"))
      (node (ref "U2") (pin "6") (pinfunction "GND_6") (pintype "power_in"))
      (node (ref "U3") (pin "2") (pinfunction "GND_2") (pintype "power_in"))
      (node (ref "U3") (pin "3") (pinfunction "GND_3") (pintype "power_in"))
      (node (ref "U3") (pin "5") (pinfunction "GND_5") (pintype "power_in"))
      (node (ref "U3") (pin "6") (pinfunction "GND_6") (pintype "power_in"))
      (node (ref "U4") (pin "2") (pinfunction "GND_2") (pintype "power_in"))
      (node (ref "U4") (pin "3") (pinfunction "GND_3") (pintype "power_in"))
      (node (ref "U4") (pin "5") (pinfunction "GND_5") (pintype "power_in"))
      (node (ref "U4") (pin "6") (pinfunction "GND_6") (pintype "power_in"))
      (node (ref "Y1") (pin "2") (pinfunction "GND_1_2") (pintype "passive"))
      (node (ref "Y1") (pin "4") (pinfunction "GND_2_4") (pintype "passive"))
    )
    (net (code "24") (name "Net-(C28-Pad2)") (class "Default")
      (node (ref "C28") (pin "2") (pinfunction "2_2") (pintype "passive"))
      (node (ref "U1") (pin "71") (pinfunction "VCAP_71") (pintype "power_in"))
    )
    (net (code "25") (name "Net-(C29-Pad2)") (class "Default")
      (node (ref "C29") (pin "2") (pinfunction "2_2") (pintype "passive"))
      (node (ref "U1") (pin "106") (pinfunction "VCAP_106") (pintype "power_in"))
    )
    (net (code "26") (name "Net-(IC2-+_IN_A)") (class "Default")
      (node (ref "IC2") (pin "3") (pinfunction "+_IN_A_3") (pintype "passive"))
      (node (ref "R17") (pin "2") (pinfunction "2_2") (pintype "passive"))
    )
    (net (code "27") (name "Net-(IC2-+_IN_B)") (class "Default")
      (node (ref "IC2") (pin "5") (pinfunction "+_IN_B_5") (pintype "passive"))
      (node (ref "R15") (pin "2") (pinfunction "2_2") (pintype "passive"))
    )
    (net (code "28") (name "Net-(IC2-+_IN_C)") (class "Default")
      (node (ref "IC2") (pin "10") (pinfunction "+_IN_C_10") (pintype "passive"))
      (node (ref "R12") (pin "2") (pinfunction "2_2") (pintype "passive"))
    )
    (net (code "29") (name "Net-(IC2--IN_C)") (class "Default")
      (node (ref "IC2") (pin "9") (pinfunction "-IN_C_9") (pintype "passive"))
      (node (ref "R10") (pin "2") (pinfunction "2_2") (pintype "passive"))
      (node (ref "R13") (pin "2") (pinfunction "2_2") (pintype "passive"))
    )
    (net (code "30") (name "Net-(IC2--_IN_A)") (class "Default")
      (node (ref "IC2") (pin "2") (pinfunction "-_IN_A_2") (pintype "passive"))
      (node (ref "R19") (pin "2") (pinfunction "2_2") (pintype "passive"))
      (node (ref "R20") (pin "2") (pinfunction "2_2") (pintype "passive"))
    )
    (net (code "31") (name "Net-(IC2--_IN_B)") (class "Default")
      (node (ref "IC2") (pin "6") (pinfunction "-_IN_B_6") (pintype "passive"))
      (node (ref "R11") (pin "2") (pinfunction "2_2") (pintype "passive"))
      (node (ref "R14") (pin "1") (pinfunction "1_1") (pintype "passive"))
    )
    (net (code "32") (name "Net-(IC3-PROG)") (class "Default")
      (node (ref "IC3") (pin "6") (pinfunction "PROG_6") (pintype "passive"))
      (node (ref "R8") (pin "2") (pinfunction "2_2") (pintype "passive"))
    )
    (net (code "33") (name "Net-(IC3-STAT1)") (class "Default")
      (node (ref "IC3") (pin "3") (pinfunction "STAT1_3") (pintype "passive"))
      (node (ref "R24") (pin "1") (pinfunction "1_1") (pintype "passive"))
    )
    (net (code "34") (name "Net-(IC3-STAT2)") (class "Default")
      (node (ref "IC3") (pin "4") (pinfunction "STAT2_4") (pintype "passive"))
      (node (ref "R25") (pin "1") (pinfunction "1_1") (pintype "passive"))
    )
    (net (code "35") (name "Net-(IC3-THERM)") (class "Default")
      (node (ref "IC3") (pin "8") (pinfunction "THERM_8") (pintype "passive"))
      (node (ref "RT1") (pin "2") (pinfunction "2_2") (pintype "passive"))
    )
    (net (code "36") (name "Net-(IC3-~{PG(}TE))") (class "Default")
      (node (ref "IC3") (pin "7") (pinfunction "~{PG(}TE)_7") (pintype "passive"))
      (node (ref "R26") (pin "1") (pinfunction "1_1") (pintype "passive"))
    )
    (net (code "37") (name "Net-(J1-PadA5)") (class "Default")
      (node (ref "J1") (pin "A5") (pinfunction "A5_A5") (pintype "passive"))
      (node (ref "R7") (pin "2") (pinfunction "2_2") (pintype "passive"))
    )
    (net (code "38") (name "Net-(J1-PadB5)") (class "Default")
      (node (ref "J1") (pin "B5") (pinfunction "B5_B5") (pintype "passive"))
      (node (ref "R6") (pin "1") (pinfunction "1_1") (pintype "passive"))
    )
    (net (code "39") (name "Net-(J1-PadMP1)") (class "Default")
      (node (ref "J1") (pin "MP1") (pinfunction "MP1_MP1") (pintype "passive"))
      (node (ref "J1") (pin "MP2") (pinfunction "MP2_MP2") (pintype "passive"))
      (node (ref "J1") (pin "MP3") (pinfunction "MP3_MP3") (pintype "passive"))
      (node (ref "J1") (pin "MP4") (pinfunction "MP4_MP4") (pintype "passive"))
      (node (ref "R28") (pin "2") (pinfunction "2_2") (pintype "passive"))
    )
    (net (code "40") (name "Net-(J2-CD{slash}DAT3)") (class "Default")
      (node (ref "J2") (pin "2") (pinfunction "CD/DAT3_2") (pintype "passive"))
      (node (ref "R4") (pin "1") (pinfunction "1_1") (pintype "passive"))
      (node (ref "U1") (pin "112") (pinfunction "PC11_112") (pintype "bidirectional"))
    )
    (net (code "41") (name "Net-(J2-CLK)") (class "Default")
      (node (ref "J2") (pin "5") (pinfunction "CLK_5") (pintype "passive"))
      (node (ref "U1") (pin "113") (pinfunction "PC12_113") (pintype "bidirectional"))
    )
    (net (code "42") (name "Net-(J2-CMD)") (class "Default")
      (node (ref "J2") (pin "3") (pinfunction "CMD_3") (pintype "passive"))
      (node (ref "R5") (pin "1") (pinfunction "1_1") (pintype "passive"))
      (node (ref "U1") (pin "116") (pinfunction "PD2_116") (pintype "bidirectional"))
    )
    (net (code "43") (name "Net-(J2-DAT0)") (class "Default")
      (node (ref "J2") (pin "7") (pinfunction "DAT0_7") (pintype "passive"))
      (node (ref "R27") (pin "1") (pinfunction "1_1") (pintype "passive"))
      (node (ref "U1") (pin "74") (pinfunction "PB13_74") (pintype "bidirectional"))
    )
    (net (code "44") (name "Net-(J2-DAT1)") (class "Default")
      (node (ref "J2") (pin "8") (pinfunction "DAT1_8") (pintype "passive"))
      (node (ref "R2") (pin "1") (pinfunction "1_1") (pintype "passive"))
      (node (ref "U1") (pin "99") (pinfunction "PC9_99") (pintype "bidirectional"))
    )
    (net (code "45") (name "Net-(J2-DAT2)") (class "Default")
      (node (ref "J2") (pin "1") (pinfunction "DAT2_1") (pintype "passive"))
      (node (ref "R3") (pin "1") (pinfunction "1_1") (pintype "passive"))
      (node (ref "U1") (pin "111") (pinfunction "PC10_111") (pintype "bidirectional"))
    )
    (net (code "46") (name "Net-(LED1-A)") (class "Default")
      (node (ref "LED1") (pin "2") (pinfunction "A_2") (pintype "passive"))
      (node (ref "R1") (pin "2") (pinfunction "2_2") (pintype "passive"))
    )
    (net (code "47") (name "Net-(LED2-K)") (class "Default")
      (node (ref "LED2") (pin "1") (pinfunction "K_1") (pintype "passive"))
      (node (ref "R24") (pin "2") (pinfunction "2_2") (pintype "passive"))
    )
    (net (code "48") (name "Net-(LED3-K)") (class "Default")
      (node (ref "LED3") (pin "1") (pinfunction "K_1") (pintype "passive"))
      (node (ref "R26") (pin "2") (pinfunction "2_2") (pintype "passive"))
    )
    (net (code "49") (name "Net-(LED4-K)") (class "Default")
      (node (ref "LED4") (pin "1") (pinfunction "K_1") (pintype "passive"))
      (node (ref "R25") (pin "2") (pinfunction "2_2") (pintype "passive"))
    )
    (net (code "50") (name "Net-(R8-Pad1)") (class "Default")
      (node (ref "R8") (pin "1") (pinfunction "1_1") (pintype "passive"))
      (node (ref "R9") (pin "1") (pinfunction "1_1") (pintype "passive"))
    )
    (net (code "51") (name "Net-(U1A-VBAT)") (class "Default")
      (node (ref "J7") (pin "1") (pinfunction "1_1") (pintype "passive"))
      (node (ref "U1") (pin "6") (pinfunction "VBAT_6") (pintype "power_in"))
    )
    (net (code "52") (name "Net-(U1C-PDR_ON)") (class "Default")
      (node (ref "R18") (pin "1") (pinfunction "1_1") (pintype "passive"))
      (node (ref "U1") (pin "143") (pinfunction "PDR_ON_143") (pintype "input"))
    )
    (net (code "53") (name "Net-(U2-OUTPUT)") (class "Default")
      (node (ref "R17") (pin "1") (pinfunction "1_1") (pintype "passive"))
      (node (ref "U2") (pin "1") (pinfunction "OUTPUT_1") (pintype "output"))
    )
    (net (code "54") (name "Net-(U3-OUTPUT)") (class "Default")
      (node (ref "R15") (pin "1") (pinfunction "1_1") (pintype "passive"))
      (node (ref "U3") (pin "1") (pinfunction "OUTPUT_1") (pintype "output"))
    )
    (net (code "55") (name "Net-(U4-OUTPUT)") (class "Default")
      (node (ref "R12") (pin "1") (pinfunction "1_1") (pintype "passive"))
      (node (ref "U4") (pin "1") (pinfunction "OUTPUT_1") (pintype "output"))
    )
    (net (code "56") (name "VBUS") (class "Default")
      (node (ref "C3") (pin "2") (pinfunction "2_2") (pintype "passive"))
      (node (ref "D1") (pin "2") (pinfunction "A_2") (pintype "passive"))
      (node (ref "IC3") (pin "1") (pinfunction "VDD_1_1") (pintype "passive"))
      (node (ref "IC3") (pin "2") (pinfunction "VDD_2_2") (pintype "passive"))
      (node (ref "J1") (pin "A4") (pinfunction "A4_A4") (pintype "passive"))
      (node (ref "J1") (pin "A9") (pinfunction "A9_A9") (pintype "passive"))
      (node (ref "J1") (pin "B4") (pinfunction "B4_B4") (pintype "passive"))
      (node (ref "J1") (pin "B9") (pinfunction "B9_B9") (pintype "passive"))
      (node (ref "J4") (pin "2") (pinfunction "2_2") (pintype "passive"))
      (node (ref "J8") (pin "2") (pinfunction "2_2") (pintype "passive"))
      (node (ref "LED2") (pin "2") (pinfunction "A_2") (pintype "passive"))
      (node (ref "LED3") (pin "2") (pinfunction "A_2") (pintype "passive"))
      (node (ref "LED4") (pin "2") (pinfunction "A_2") (pintype "passive"))
      (node (ref "U1") (pin "101") (pinfunction "PA9_101") (pintype "bidirectional"))
    )
    (net (code "57") (name "unconnected-(IC2-+_IN_D-Pad12)") (class "Default")
      (node (ref "IC2") (pin "12") (pinfunction "+_IN_D_12") (pintype "passive+no_connect"))
    )
    (net (code "58") (name "unconnected-(IC2--_IN_D-Pad13)") (class "Default")
      (node (ref "IC2") (pin "13") (pinfunction "-_IN_D_13") (pintype "passive+no_connect"))
    )
    (net (code "59") (name "unconnected-(IC2-OUT_D-Pad14)") (class "Default")
      (node (ref "IC2") (pin "14") (pinfunction "OUT_D_14") (pintype "passive+no_connect"))
    )
    (net (code "60") (name "unconnected-(J1-PadA8)") (class "Default")
      (node (ref "J1") (pin "A8") (pinfunction "A8_A8") (pintype "passive+no_connect"))
    )
    (net (code "61") (name "unconnected-(J1-PadB8)") (class "Default")
      (node (ref "J1") (pin "B8") (pinfunction "B8_B8") (pintype "passive+no_connect"))
    )
    (net (code "62") (name "unconnected-(J2-CD-Pad9)") (class "Default")
      (node (ref "J2") (pin "9") (pinfunction "CD_9") (pintype "passive+no_connect"))
    )
    (net (code "63") (name "unconnected-(S2-Pad4)") (class "Default")
      (node (ref "S2") (pin "4") (pinfunction "4_4") (pintype "passive+no_connect"))
    )
    (net (code "64") (name "unconnected-(S2-Pad5)") (class "Default")
      (node (ref "S2") (pin "5") (pinfunction "5_5") (pintype "passive+no_connect"))
    )
    (net (code "65") (name "unconnected-(S2-Pad6)") (class "Default")
      (node (ref "S2") (pin "6") (pinfunction "6_6") (pintype "passive+no_connect"))
    )
    (net (code "66") (name "unconnected-(U1B-PA0-Pad34)") (class "Default")
      (node (ref "U1") (pin "34") (pinfunction "PA0_34") (pintype "bidirectional"))
    )
    (net (code "67") (name "unconnected-(U1B-PA1-Pad35)") (class "Default")
      (node (ref "U1") (pin "35") (pinfunction "PA1_35") (pintype "bidirectional"))
    )
    (net (code "68") (name "unconnected-(U1B-PA2-Pad36)") (class "Default")
      (node (ref "U1") (pin "36") (pinfunction "PA2_36") (pintype "bidirectional"))
    )
    (net (code "69") (name "unconnected-(U1B-PA3-Pad37)") (class "Default")
      (node (ref "U1") (pin "37") (pinfunction "PA3_37") (pintype "bidirectional"))
    )
    (net (code "70") (name "unconnected-(U1B-PA4-Pad40)") (class "Default")
      (node (ref "U1") (pin "40") (pinfunction "PA4_40") (pintype "bidirectional"))
    )
    (net (code "71") (name "unconnected-(U1B-PA5-Pad41)") (class "Default")
      (node (ref "U1") (pin "41") (pinfunction "PA5_41") (pintype "bidirectional"))
    )
    (net (code "72") (name "unconnected-(U1B-PA7-Pad43)") (class "Default")
      (node (ref "U1") (pin "43") (pinfunction "PA7_43") (pintype "bidirectional"))
    )
    (net (code "73") (name "unconnected-(U1B-PA8-Pad100)") (class "Default")
      (node (ref "U1") (pin "100") (pinfunction "PA8_100") (pintype "bidirectional"))
    )
    (net (code "74") (name "unconnected-(U1B-PA10-Pad102)") (class "Default")
      (node (ref "U1") (pin "102") (pinfunction "PA10_102") (pintype "bidirectional"))
    )
    (net (code "75") (name "unconnected-(U1B-PA15-Pad110)") (class "Default")
      (node (ref "U1") (pin "110") (pinfunction "PA15_110") (pintype "bidirectional"))
    )
    (net (code "76") (name "unconnected-(U1B-PB0-Pad46)") (class "Default")
      (node (ref "U1") (pin "46") (pinfunction "PB0_46") (pintype "bidirectional"))
    )
    (net (code "77") (name "unconnected-(U1B-PB1-Pad47)") (class "Default")
      (node (ref "U1") (pin "47") (pinfunction "PB1_47") (pintype "bidirectional"))
    )
    (net (code "78") (name "unconnected-(U1B-PB2-Pad48)") (class "Default")
      (node (ref "U1") (pin "48") (pinfunction "PB2_48") (pintype "bidirectional"))
    )
    (net (code "79") (name "unconnected-(U1B-PB4-Pad134)") (class "Default")
      (node (ref "U1") (pin "134") (pinfunction "PB4_134") (pintype "bidirectional"))
    )
    (net (code "80") (name "unconnected-(U1B-PB5-Pad135)") (class "Default")
      (node (ref "U1") (pin "135") (pinfunction "PB5_135") (pintype "bidirectional"))
    )
    (net (code "81") (name "unconnected-(U1B-PB10-Pad69)") (class "Default")
      (node (ref "U1") (pin "69") (pinfunction "PB10_69") (pintype "bidirectional"))
    )
    (net (code "82") (name "unconnected-(U1B-PB11-Pad70)") (class "Default")
      (node (ref "U1") (pin "70") (pinfunction "PB11_70") (pintype "bidirectional"))
    )
    (net (code "83") (name "unconnected-(U1B-PB12-Pad73)") (class "Default")
      (node (ref "U1") (pin "73") (pinfunction "PB12_73") (pintype "bidirectional"))
    )
    (net (code "84") (name "unconnected-(U1B-PB14-Pad75)") (class "Default")
      (node (ref "U1") (pin "75") (pinfunction "PB14_75") (pintype "bidirectional"))
    )
    (net (code "85") (name "unconnected-(U1B-PB15-Pad76)") (class "Default")
      (node (ref "U1") (pin "76") (pinfunction "PB15_76") (pintype "bidirectional"))
    )
    (net (code "86") (name "unconnected-(U1B-PC0-Pad26)") (class "Default")
      (node (ref "U1") (pin "26") (pinfunction "PC0_26") (pintype "bidirectional"))
    )
    (net (code "87") (name "unconnected-(U1B-PC1-Pad27)") (class "Default")
      (node (ref "U1") (pin "27") (pinfunction "PC1_27") (pintype "bidirectional"))
    )
    (net (code "88") (name "unconnected-(U1B-PC2_C-Pad28)") (class "Default")
      (node (ref "U1") (pin "28") (pinfunction "PC2_C_28") (pintype "bidirectional"))
    )
    (net (code "89") (name "unconnected-(U1B-PC3_C-Pad29)") (class "Default")
      (node (ref "U1") (pin "29") (pinfunction "PC3_C_29") (pintype "bidirectional"))
    )
    (net (code "90") (name "unconnected-(U1B-PC5-Pad45)") (class "Default")
      (node (ref "U1") (pin "45") (pinfunction "PC5_45") (pintype "bidirectional"))
    )
    (net (code "91") (name "unconnected-(U1B-PC6-Pad96)") (class "Default")
      (node (ref "U1") (pin "96") (pinfunction "PC6_96") (pintype "bidirectional"))
    )
    (net (code "92") (name "unconnected-(U1B-PC7-Pad97)") (class "Default")
      (node (ref "U1") (pin "97") (pinfunction "PC7_97") (pintype "bidirectional"))
    )
    (net (code "93") (name "unconnected-(U1B-PC8-Pad98)") (class "Default")
      (node (ref "U1") (pin "98") (pinfunction "PC8_98") (pintype "bidirectional"))
    )
    (net (code "94") (name "unconnected-(U1B-PC13-Pad7)") (class "Default")
      (node (ref "U1") (pin "7") (pinfunction "PC13_7") (pintype "bidirectional"))
    )
    (net (code "95") (name "unconnected-(U1B-PC14-OSC32_IN-Pad8)") (class "Default")
      (node (ref "U1") (pin "8") (pinfunction "PC14-OSC32_IN_8") (pintype "bidirectional"))
    )
    (net (code "96") (name "unconnected-(U1B-PC15-OSC32_OUT-Pad9)") (class "Default")
      (node (ref "U1") (pin "9") (pinfunction "PC15-OSC32_OUT_9") (pintype "bidirectional"))
    )
    (net (code "97") (name "unconnected-(U1B-PD0-Pad114)") (class "Default")
      (node (ref "U1") (pin "114") (pinfunction "PD0_114") (pintype "bidirectional"))
    )
    (net (code "98") (name "unconnected-(U1B-PD1-Pad115)") (class "Default")
      (node (ref "U1") (pin "115") (pinfunction "PD1_115") (pintype "bidirectional"))
    )
    (net (code "99") (name "unconnected-(U1B-PD3-Pad117)") (class "Default")
      (node (ref "U1") (pin "117") (pinfunction "PD3_117") (pintype "bidirectional"))
    )
    (net (code "100") (name "unconnected-(U1B-PD4-Pad118)") (class "Default")
      (node (ref "U1") (pin "118") (pinfunction "PD4_118") (pintype "bidirectional"))
    )
    (net (code "101") (name "unconnected-(U1B-PD5-Pad119)") (class "Default")
      (node (ref "U1") (pin "119") (pinfunction "PD5_119") (pintype "bidirectional"))
    )
    (net (code "102") (name "unconnected-(U1B-PD6-Pad122)") (class "Default")
      (node (ref "U1") (pin "122") (pinfunction "PD6_122") (pintype "bidirectional"))
    )
    (net (code "103") (name "unconnected-(U1B-PD7-Pad123)") (class "Default")
      (node (ref "U1") (pin "123") (pinfunction "PD7_123") (pintype "bidirectional"))
    )
    (net (code "104") (name "unconnected-(U1B-PD8-Pad77)") (class "Default")
      (node (ref "U1") (pin "77") (pinfunction "PD8_77") (pintype "bidirectional"))
    )
    (net (code "105") (name "unconnected-(U1B-PD9-Pad78)") (class "Default")
      (node (ref "U1") (pin "78") (pinfunction "PD9_78") (pintype "bidirectional"))
    )
    (net (code "106") (name "unconnected-(U1B-PD10-Pad79)") (class "Default")
      (node (ref "U1") (pin "79") (pinfunction "PD10_79") (pintype "bidirectional"))
    )
    (net (code "107") (name "unconnected-(U1B-PD11-Pad80)") (class "Default")
      (node (ref "U1") (pin "80") (pinfunction "PD11_80") (pintype "bidirectional"))
    )
    (net (code "108") (name "unconnected-(U1B-PD12-Pad81)") (class "Default")
      (node (ref "U1") (pin "81") (pinfunction "PD12_81") (pintype "bidirectional"))
    )
    (net (code "109") (name "unconnected-(U1B-PD13-Pad82)") (class "Default")
      (node (ref "U1") (pin "82") (pinfunction "PD13_82") (pintype "bidirectional"))
    )
    (net (code "110") (name "unconnected-(U1B-PD14-Pad85)") (class "Default")
      (node (ref "U1") (pin "85") (pinfunction "PD14_85") (pintype "bidirectional"))
    )
    (net (code "111") (name "unconnected-(U1B-PD15-Pad86)") (class "Default")
      (node (ref "U1") (pin "86") (pinfunction "PD15_86") (pintype "bidirectional"))
    )
    (net (code "112") (name "unconnected-(U1C-PE0-Pad141)") (class "Default")
      (node (ref "U1") (pin "141") (pinfunction "PE0_141") (pintype "bidirectional"))
    )
    (net (code "113") (name "unconnected-(U1C-PE1-Pad142)") (class "Default")
      (node (ref "U1") (pin "142") (pinfunction "PE1_142") (pintype "bidirectional"))
    )
    (net (code "114") (name "unconnected-(U1C-PE2-Pad1)") (class "Default")
      (node (ref "U1") (pin "1") (pinfunction "PE2_1") (pintype "bidirectional"))
    )
    (net (code "115") (name "unconnected-(U1C-PE3-Pad2)") (class "Default")
      (node (ref "U1") (pin "2") (pinfunction "PE3_2") (pintype "bidirectional"))
    )
    (net (code "116") (name "unconnected-(U1C-PE4-Pad3)") (class "Default")
      (node (ref "U1") (pin "3") (pinfunction "PE4_3") (pintype "bidirectional"))
    )
    (net (code "117") (name "unconnected-(U1C-PE5-Pad4)") (class "Default")
      (node (ref "U1") (pin "4") (pinfunction "PE5_4") (pintype "bidirectional"))
    )
    (net (code "118") (name "unconnected-(U1C-PE6-Pad5)") (class "Default")
      (node (ref "U1") (pin "5") (pinfunction "PE6_5") (pintype "bidirectional"))
    )
    (net (code "119") (name "unconnected-(U1C-PE7-Pad58)") (class "Default")
      (node (ref "U1") (pin "58") (pinfunction "PE7_58") (pintype "bidirectional"))
    )
    (net (code "120") (name "unconnected-(U1C-PE8-Pad59)") (class "Default")
      (node (ref "U1") (pin "59") (pinfunction "PE8_59") (pintype "bidirectional"))
    )
    (net (code "121") (name "unconnected-(U1C-PE9-Pad60)") (class "Default")
      (node (ref "U1") (pin "60") (pinfunction "PE9_60") (pintype "bidirectional"))
    )
    (net (code "122") (name "unconnected-(U1C-PE10-Pad63)") (class "Default")
      (node (ref "U1") (pin "63") (pinfunction "PE10_63") (pintype "bidirectional"))
    )
    (net (code "123") (name "unconnected-(U1C-PE11-Pad64)") (class "Default")
      (node (ref "U1") (pin "64") (pinfunction "PE11_64") (pintype "bidirectional"))
    )
    (net (code "124") (name "unconnected-(U1C-PE12-Pad65)") (class "Default")
      (node (ref "U1") (pin "65") (pinfunction "PE12_65") (pintype "bidirectional"))
    )
    (net (code "125") (name "unconnected-(U1C-PE13-Pad66)") (class "Default")
      (node (ref "U1") (pin "66") (pinfunction "PE13_66") (pintype "bidirectional"))
    )
    (net (code "126") (name "unconnected-(U1C-PE14-Pad67)") (class "Default")
      (node (ref "U1") (pin "67") (pinfunction "PE14_67") (pintype "bidirectional"))
    )
    (net (code "127") (name "unconnected-(U1C-PE15-Pad68)") (class "Default")
      (node (ref "U1") (pin "68") (pinfunction "PE15_68") (pintype "bidirectional"))
    )
    (net (code "128") (name "unconnected-(U1C-PF2-Pad12)") (class "Default")
      (node (ref "U1") (pin "12") (pinfunction "PF2_12") (pintype "bidirectional"))
    )
    (net (code "129") (name "unconnected-(U1C-PF3-Pad13)") (class "Default")
      (node (ref "U1") (pin "13") (pinfunction "PF3_13") (pintype "bidirectional"))
    )
    (net (code "130") (name "unconnected-(U1C-PF4-Pad14)") (class "Default")
      (node (ref "U1") (pin "14") (pinfunction "PF4_14") (pintype "bidirectional"))
    )
    (net (code "131") (name "unconnected-(U1C-PF5-Pad15)") (class "Default")
      (node (ref "U1") (pin "15") (pinfunction "PF5_15") (pintype "bidirectional"))
    )
    (net (code "132") (name "unconnected-(U1C-PF6-Pad18)") (class "Default")
      (node (ref "U1") (pin "18") (pinfunction "PF6_18") (pintype "bidirectional"))
    )
    (net (code "133") (name "unconnected-(U1C-PF7-Pad19)") (class "Default")
      (node (ref "U1") (pin "19") (pinfunction "PF7_19") (pintype "bidirectional"))
    )
    (net (code "134") (name "unconnected-(U1C-PF8-Pad20)") (class "Default")
      (node (ref "U1") (pin "20") (pinfunction "PF8_20") (pintype "bidirectional"))
    )
    (net (code "135") (name "unconnected-(U1C-PF9-Pad21)") (class "Default")
      (node (ref "U1") (pin "21") (pinfunction "PF9_21") (pintype "bidirectional"))
    )
    (net (code "136") (name "unconnected-(U1C-PF10-Pad22)") (class "Default")
      (node (ref "U1") (pin "22") (pinfunction "PF10_22") (pintype "bidirectional"))
    )
    (net (code "137") (name "unconnected-(U1C-PF12-Pad50)") (class "Default")
      (node (ref "U1") (pin "50") (pinfunction "PF12_50") (pintype "bidirectional"))
    )
    (net (code "138") (name "unconnected-(U1C-PF13-Pad53)") (class "Default")
      (node (ref "U1") (pin "53") (pinfunction "PF13_53") (pintype "bidirectional"))
    )
    (net (code "139") (name "unconnected-(U1C-PF14-Pad54)") (class "Default")
      (node (ref "U1") (pin "54") (pinfunction "PF14_54") (pintype "bidirectional"))
    )
    (net (code "140") (name "unconnected-(U1C-PF15-Pad55)") (class "Default")
      (node (ref "U1") (pin "55") (pinfunction "PF15_55") (pintype "bidirectional"))
    )
    (net (code "141") (name "unconnected-(U1C-PG0-Pad56)") (class "Default")
      (node (ref "U1") (pin "56") (pinfunction "PG0_56") (pintype "bidirectional"))
    )
    (net (code "142") (name "unconnected-(U1C-PG1-Pad57)") (class "Default")
      (node (ref "U1") (pin "57") (pinfunction "PG1_57") (pintype "bidirectional"))
    )
    (net (code "143") (name "unconnected-(U1C-PG2-Pad87)") (class "Default")
      (node (ref "U1") (pin "87") (pinfunction "PG2_87") (pintype "bidirectional"))
    )
    (net (code "144") (name "unconnected-(U1C-PG3-Pad88)") (class "Default")
      (node (ref "U1") (pin "88") (pinfunction "PG3_88") (pintype "bidirectional"))
    )
    (net (code "145") (name "unconnected-(U1C-PG4-Pad89)") (class "Default")
      (node (ref "U1") (pin "89") (pinfunction "PG4_89") (pintype "bidirectional"))
    )
    (net (code "146") (name "unconnected-(U1C-PG5-Pad90)") (class "Default")
      (node (ref "U1") (pin "90") (pinfunction "PG5_90") (pintype "bidirectional"))
    )
    (net (code "147") (name "unconnected-(U1C-PG6-Pad91)") (class "Default")
      (node (ref "U1") (pin "91") (pinfunction "PG6_91") (pintype "bidirectional"))
    )
    (net (code "148") (name "unconnected-(U1C-PG7-Pad92)") (class "Default")
      (node (ref "U1") (pin "92") (pinfunction "PG7_92") (pintype "bidirectional"))
    )
    (net (code "149") (name "unconnected-(U1C-PG8-Pad93)") (class "Default")
      (node (ref "U1") (pin "93") (pinfunction "PG8_93") (pintype "bidirectional"))
    )
    (net (code "150") (name "unconnected-(U1C-PG9-Pad124)") (class "Default")
      (node (ref "U1") (pin "124") (pinfunction "PG9_124") (pintype "bidirectional"))
    )
    (net (code "151") (name "unconnected-(U1C-PG10-Pad125)") (class "Default")
      (node (ref "U1") (pin "125") (pinfunction "PG10_125") (pintype "bidirectional"))
    )
    (net (code "152") (name "unconnected-(U1C-PG11-Pad126)") (class "Default")
      (node (ref "U1") (pin "126") (pinfunction "PG11_126") (pintype "bidirectional"))
    )
    (net (code "153") (name "unconnected-(U1C-PG12-Pad127)") (class "Default")
      (node (ref "U1") (pin "127") (pinfunction "PG12_127") (pintype "bidirectional"))
    )
    (net (code "154") (name "unconnected-(U1C-PG13-Pad128)") (class "Default")
      (node (ref "U1") (pin "128") (pinfunction "PG13_128") (pintype "bidirectional"))
    )
    (net (code "155") (name "unconnected-(U1C-PG14-Pad129)") (class "Default")
      (node (ref "U1") (pin "129") (pinfunction "PG14_129") (pintype "bidirectional"))
    )
    (net (code "156") (name "unconnected-(U1C-PG15-Pad132)") (class "Default")
      (node (ref "U1") (pin "132") (pinfunction "PG15_132") (pintype "bidirectional"))
    )
  )
)
